# 03_-_Interfaces.net
KiCad netlist of a schematic drawn in Altium Designer
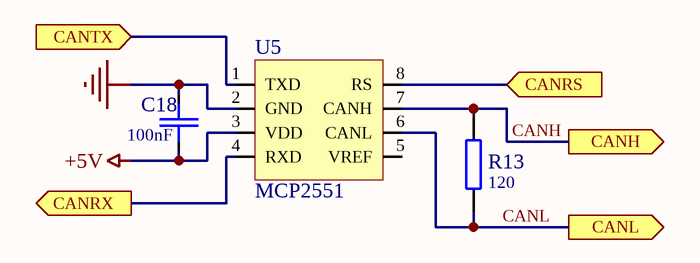
[diagram p0: 03 - Interfaces.SchDoc]

(export (version "E")
  (design (tool "Eeschema 10.0.6"))
  (components
    (comp (ref "C18")
      (value "100nF")
      (footprint "CAP: 0805")
      (description "SMD-0805")
      (libsource (lib "RCL_SMD_Integrated_Library") (part "C-0805"))
    )
    (comp (ref "R13")
      (value "120")
      (footprint "RES: 0805")
      (description "SMD 0805 0.1W 5% 150V")
      (libsource (lib "RCL_SMD_Integrated_Library") (part "R-0805"))
    )
    (comp (ref "U5")
      (value "MCP2551")
      (footprint "SOIC-8N")
      (libsource (lib "stm32_Integrated_Library") (part "MCP2551"))
    )
  )
  (nets
    (net (code "1") (name "+5V") (class "Default")
      (node (ref "C18") (pin "1") (pinfunction "1_1") (pintype "passive"))
      (node (ref "U5") (pin "3") (pinfunction "VDD_3") (pintype "passive"))
    )
    (net (code "2") (name "/CANH") (class "Default")
      (node (ref "R13") (pin "2") (pinfunction "2_2") (pintype "passive"))
      (node (ref "U5") (pin "7") (pinfunction "CANH_7") (pintype "passive"))
    )
    (net (code "3") (name "/CANL") (class "Default")
      (node (ref "R13") (pin "1") (pinfunction "1_1") (pintype "passive"))
      (node (ref "U5") (pin "6") (pinfunction "CANL_6") (pintype "passive"))
    )
    (net (code "4") (name "/CANRS") (class "Default")
      (node (ref "U5") (pin "8") (pinfunction "RS_8") (pintype "passive"))
    )
    (net (code "5") (name "/CANRX") (class "Default")
      (node (ref "U5") (pin "4") (pinfunction "RXD_4") (pintype "passive"))
    )
    (net (code "6") (name "/CANTX") (class "Default")
      (node (ref "U5") (pin "1") (pinfunction "TXD_1") (pintype "passive"))
    )
    (net (code "7") (name "GND") (class "Default")
      (node (ref "C18") (pin "2") (pinfunction "2_2") (pintype "passive"))
      (node (ref "U5") (pin "2") (pinfunction "GND_2") (pintype "passive"))
    )
    (net (code "8") (name "unconnected-(U5-VREF-Pad5)") (class "Default")
      (node (ref "U5") (pin "5") (pinfunction "VREF_5") (pintype "passive"))
    )
  )
)
